# bldc_robot_main_adapter_board.net
KiCad netlist of a schematic drawn in Altium Designer
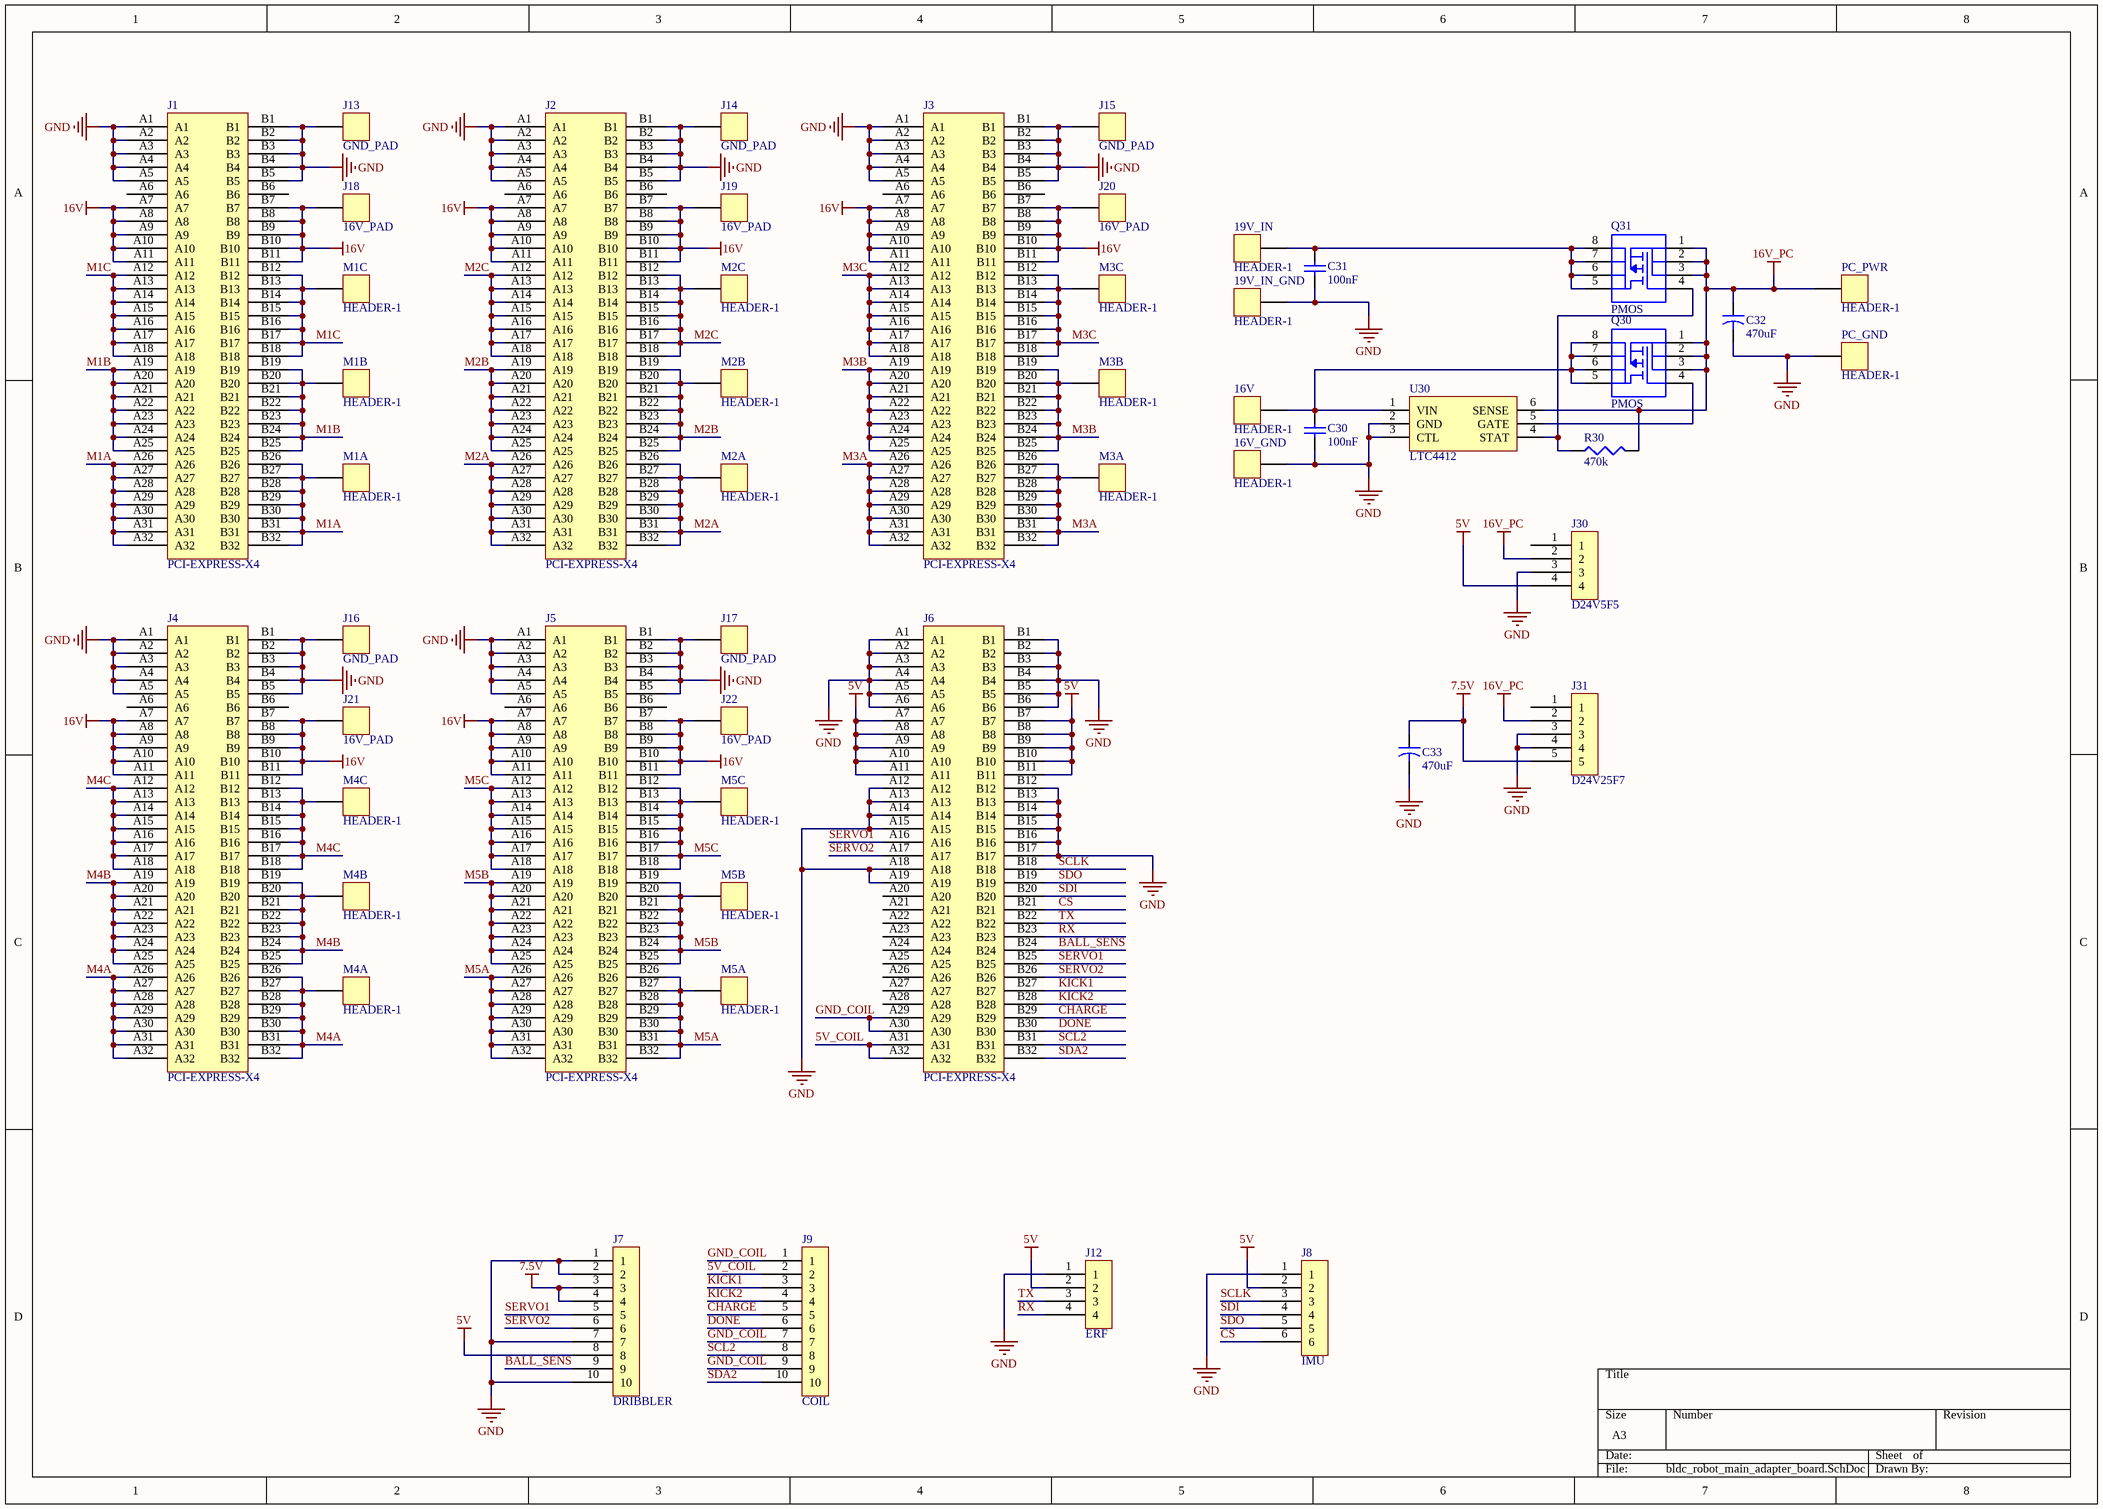
[diagram p0: bldc_robot_main_adapter_board.SchDoc]

(export (version "E")
  (design (tool "Eeschema 10.0.6"))
  (components
    (comp (ref "16V") (value "HEADER-1") (footprint "POWER-VIA") (libsource (lib "") (part "HEADER-1_1")))
    (comp (ref "16V_GND") (value "HEADER-1") (footprint "POWER-VIA") (libsource (lib "") (part "HEADER-1_1")))
    (comp (ref "19V_IN") (value "HEADER-1") (footprint "POWER-VIA") (libsource (lib "") (part "HEADER-1_1")))
    (comp (ref "19V_IN_GND")
      (value "HEADER-1")
      (footprint "POWER-VIA")
      (libsource (lib "") (part "HEADER-1_1"))
    )
    (comp (ref "C30")
      (value "100nF")
      (footprint "1608[0603]")
      (description "Capacitor (Semiconductor SIM Model)")
      (fields (field (name "PUBLISHER") "Altium Limited"))
      (libsource (lib "Miscellaneous Devices") (part "Cap Semi"))
    )
    (comp (ref "C31")
      (value "100nF")
      (footprint "1608[0603]")
      (description "Capacitor (Semiconductor SIM Model)")
      (fields (field (name "PUBLISHER") "Altium Limited"))
      (libsource (lib "Miscellaneous Devices") (part "Cap Semi"))
    )
    (comp (ref "C32")
      (value "470uF")
      (footprint "CAPR5-4X5")
      (description "Capacitor")
      (fields (field (name "PUBLISHER") "Altium Limited"))
      (libsource (lib "Miscellaneous Devices") (part "Cap2"))
    )
    (comp (ref "C33")
      (value "470uF")
      (footprint "CAPR5-4X5")
      (description "Capacitor")
      (fields (field (name "PUBLISHER") "Altium Limited"))
      (libsource (lib "Miscellaneous Devices") (part "Cap2"))
    )
    (comp (ref "J1")
      (value "PCI-EXPRESS-X4")
      (footprint "PCI-EXPRESS-X4-SOCKET")
      (libsource (lib "connectors") (part "PCI-EXPRESS-X4"))
    )
    (comp (ref "J2")
      (value "PCI-EXPRESS-X4")
      (footprint "PCI-EXPRESS-X4-SOCKET")
      (libsource (lib "connectors") (part "PCI-EXPRESS-X4"))
    )
    (comp (ref "J3")
      (value "PCI-EXPRESS-X4")
      (footprint "PCI-EXPRESS-X4-SOCKET")
      (libsource (lib "connectors") (part "PCI-EXPRESS-X4"))
    )
    (comp (ref "J4")
      (value "PCI-EXPRESS-X4")
      (footprint "PCI-EXPRESS-X4-SOCKET")
      (libsource (lib "connectors") (part "PCI-EXPRESS-X4"))
    )
    (comp (ref "J5")
      (value "PCI-EXPRESS-X4")
      (footprint "PCI-EXPRESS-X4-SOCKET")
      (libsource (lib "connectors") (part "PCI-EXPRESS-X4"))
    )
    (comp (ref "J6")
      (value "PCI-EXPRESS-X4")
      (footprint "PCI-EXPRESS-X4-SOCKET")
      (libsource (lib "connectors") (part "PCI-EXPRESS-X4"))
    )
    (comp (ref "J7")
      (value "DRIBBLER")
      (footprint "MICRO-MATCH-10")
      (libsource (lib "connectors") (part "HEADER-10"))
    )
    (comp (ref "J8")
      (value "IMU")
      (footprint "MICRO-MATCH-6")
      (libsource (lib "connectors") (part "HEADER-6"))
    )
    (comp (ref "J9")
      (value "COIL")
      (footprint "MICRO-MATCH-10")
      (libsource (lib "connectors") (part "HEADER-10"))
    )
    (comp (ref "J12")
      (value "ERF")
      (footprint "MICRO-MATCH-4")
      (libsource (lib "connectors") (part "HEADER-4"))
    )
    (comp (ref "J13")
      (value "GND_PAD")
      (footprint "POWER-PAD")
      (libsource (lib "connectors") (part "HEADER-1"))
    )
    (comp (ref "J14")
      (value "GND_PAD")
      (footprint "POWER-PAD")
      (libsource (lib "connectors") (part "HEADER-1"))
    )
    (comp (ref "J15")
      (value "GND_PAD")
      (footprint "POWER-PAD")
      (libsource (lib "connectors") (part "HEADER-1"))
    )
    (comp (ref "J16")
      (value "GND_PAD")
      (footprint "POWER-PAD")
      (libsource (lib "connectors") (part "HEADER-1"))
    )
    (comp (ref "J17")
      (value "GND_PAD")
      (footprint "POWER-PAD")
      (libsource (lib "connectors") (part "HEADER-1"))
    )
    (comp (ref "J18")
      (value "16V_PAD")
      (footprint "POWER-PAD")
      (libsource (lib "connectors") (part "HEADER-1"))
    )
    (comp (ref "J19")
      (value "16V_PAD")
      (footprint "POWER-PAD")
      (libsource (lib "connectors") (part "HEADER-1"))
    )
    (comp (ref "J20")
      (value "16V_PAD")
      (footprint "POWER-PAD")
      (libsource (lib "connectors") (part "HEADER-1"))
    )
    (comp (ref "J21")
      (value "16V_PAD")
      (footprint "POWER-PAD")
      (libsource (lib "connectors") (part "HEADER-1"))
    )
    (comp (ref "J22")
      (value "16V_PAD")
      (footprint "POWER-PAD")
      (libsource (lib "connectors") (part "HEADER-1"))
    )
    (comp (ref "J30")
      (value "D24V5F5")
      (footprint "PIN-HEADER-4")
      (libsource (lib "connectors") (part "HEADER-4"))
    )
    (comp (ref "J31")
      (value "D24V25F7")
      (footprint "PIN-HEADER-5")
      (libsource (lib "connectors") (part "HEADER-5"))
    )
    (comp (ref "M1A")
      (value "HEADER-1")
      (footprint "2MM-BULLET-VIA")
      (libsource (lib "connectors") (part "HEADER-1"))
    )
    (comp (ref "M1B")
      (value "HEADER-1")
      (footprint "2MM-BULLET-VIA")
      (libsource (lib "connectors") (part "HEADER-1"))
    )
    (comp (ref "M1C")
      (value "HEADER-1")
      (footprint "2MM-BULLET-VIA")
      (libsource (lib "connectors") (part "HEADER-1"))
    )
    (comp (ref "M2A")
      (value "HEADER-1")
      (footprint "2MM-BULLET-VIA")
      (libsource (lib "connectors") (part "HEADER-1"))
    )
    (comp (ref "M2B")
      (value "HEADER-1")
      (footprint "2MM-BULLET-VIA")
      (libsource (lib "connectors") (part "HEADER-1"))
    )
    (comp (ref "M2C")
      (value "HEADER-1")
      (footprint "2MM-BULLET-VIA")
      (libsource (lib "connectors") (part "HEADER-1"))
    )
    (comp (ref "M3A")
      (value "HEADER-1")
      (footprint "2MM-BULLET-VIA")
      (libsource (lib "connectors") (part "HEADER-1"))
    )
    (comp (ref "M3B")
      (value "HEADER-1")
      (footprint "2MM-BULLET-VIA")
      (libsource (lib "connectors") (part "HEADER-1"))
    )
    (comp (ref "M3C")
      (value "HEADER-1")
      (footprint "2MM-BULLET-VIA")
      (libsource (lib "connectors") (part "HEADER-1"))
    )
    (comp (ref "M4A")
      (value "HEADER-1")
      (footprint "2MM-BULLET-VIA")
      (libsource (lib "connectors") (part "HEADER-1"))
    )
    (comp (ref "M4B")
      (value "HEADER-1")
      (footprint "2MM-BULLET-VIA")
      (libsource (lib "connectors") (part "HEADER-1"))
    )
    (comp (ref "M4C")
      (value "HEADER-1")
      (footprint "2MM-BULLET-VIA")
      (libsource (lib "connectors") (part "HEADER-1"))
    )
    (comp (ref "M5A")
      (value "HEADER-1")
      (footprint "2MM-BULLET-VIA")
      (libsource (lib "connectors") (part "HEADER-1"))
    )
    (comp (ref "M5B")
      (value "HEADER-1")
      (footprint "2MM-BULLET-VIA")
      (libsource (lib "connectors") (part "HEADER-1"))
    )
    (comp (ref "M5C")
      (value "HEADER-1")
      (footprint "2MM-BULLET-VIA")
      (libsource (lib "connectors") (part "HEADER-1"))
    )
    (comp (ref "PC_GND")
      (value "HEADER-1")
      (footprint "POWER-VIA")
      (libsource (lib "connectors") (part "HEADER-1"))
    )
    (comp (ref "PC_PWR")
      (value "HEADER-1")
      (footprint "POWER-VIA")
      (libsource (lib "connectors") (part "HEADER-1"))
    )
    (comp (ref "Q30") (value "PMOS") (footprint "SO8") (libsource (lib "misc") (part "PMOS")))
    (comp (ref "Q31") (value "PMOS") (footprint "SO8") (libsource (lib "misc") (part "PMOS")))
    (comp (ref "R30")
      (value "470k")
      (footprint "J1-0603")
      (description "Resistor")
      (fields (field (name "PUBLISHER") "Altium Limited"))
      (libsource (lib "Miscellaneous Devices") (part "Res3"))
    )
    (comp (ref "U30") (value "LTC4412") (footprint "TSOT-23-6") (libsource (lib "digital") (part "LTC4412")))
  )
  (nets
    (net (code "1") (name "/5V_COIL") (class "Default")
      (node (ref "J6") (pin "A31") (pinfunction "A31_A31") (pintype "passive"))
      (node (ref "J6") (pin "A32") (pinfunction "A32_A32") (pintype "passive"))
      (node (ref "J9") (pin "2") (pinfunction "2_2") (pintype "passive"))
    )
    (net (code "2") (name "/BALL_SENS") (class "Default")
      (node (ref "J6") (pin "B24") (pinfunction "B24_B24") (pintype "passive"))
      (node (ref "J7") (pin "9") (pinfunction "9_9") (pintype "passive"))
    )
    (net (code "3") (name "/CHARGE") (class "Default")
      (node (ref "J6") (pin "B29") (pinfunction "B29_B29") (pintype "passive"))
      (node (ref "J9") (pin "5") (pinfunction "5_5") (pintype "passive"))
    )
    (net (code "4") (name "/CS") (class "Default")
      (node (ref "J6") (pin "B21") (pinfunction "B21_B21") (pintype "passive"))
      (node (ref "J8") (pin "6") (pinfunction "6_6") (pintype "passive"))
    )
    (net (code "5") (name "/DONE") (class "Default")
      (node (ref "J6") (pin "B30") (pinfunction "B30_B30") (pintype "passive"))
      (node (ref "J9") (pin "6") (pinfunction "6_6") (pintype "passive"))
    )
    (net (code "6") (name "/GND_COIL") (class "Default")
      (node (ref "J6") (pin "A29") (pinfunction "A29_A29") (pintype "passive"))
      (node (ref "J6") (pin "A30") (pinfunction "A30_A30") (pintype "passive"))
      (node (ref "J9") (pin "1") (pinfunction "1_1") (pintype "passive"))
      (node (ref "J9") (pin "7") (pinfunction "7_7") (pintype "passive"))
      (node (ref "J9") (pin "9") (pinfunction "9_9") (pintype "passive"))
    )
    (net (code "7") (name "/KICK1") (class "Default")
      (node (ref "J6") (pin "B27") (pinfunction "B27_B27") (pintype "passive"))
      (node (ref "J9") (pin "3") (pinfunction "3_3") (pintype "passive"))
    )
    (net (code "8") (name "/KICK2") (class "Default")
      (node (ref "J6") (pin "B28") (pinfunction "B28_B28") (pintype "passive"))
      (node (ref "J9") (pin "4") (pinfunction "4_4") (pintype "passive"))
    )
    (net (code "9") (name "/M1A") (class "Default")
      (node (ref "J1") (pin "A26") (pinfunction "A26_A26") (pintype "passive"))
      (node (ref "J1") (pin "A27") (pinfunction "A27_A27") (pintype "passive"))
      (node (ref "J1") (pin "A28") (pinfunction "A28_A28") (pintype "passive"))
      (node (ref "J1") (pin "A29") (pinfunction "A29_A29") (pintype "passive"))
      (node (ref "J1") (pin "A30") (pinfunction "A30_A30") (pintype "passive"))
      (node (ref "J1") (pin "A31") (pinfunction "A31_A31") (pintype "passive"))
      (node (ref "J1") (pin "A32") (pinfunction "A32_A32") (pintype "passive"))
      (node (ref "J1") (pin "B26") (pinfunction "B26_B26") (pintype "passive"))
      (node (ref "J1") (pin "B27") (pinfunction "B27_B27") (pintype "passive"))
      (node (ref "J1") (pin "B28") (pinfunction "B28_B28") (pintype "passive"))
      (node (ref "J1") (pin "B29") (pinfunction "B29_B29") (pintype "passive"))
      (node (ref "J1") (pin "B30") (pinfunction "B30_B30") (pintype "passive"))
      (node (ref "J1") (pin "B31") (pinfunction "B31_B31") (pintype "passive"))
      (node (ref "J1") (pin "B32") (pinfunction "B32_B32") (pintype "passive"))
      (node (ref "M1A") (pin "1") (pinfunction "1_1") (pintype "passive"))
    )
    (net (code "10") (name "/M1B") (class "Default")
      (node (ref "J1") (pin "A19") (pinfunction "A19_A19") (pintype "passive"))
      (node (ref "J1") (pin "A20") (pinfunction "A20_A20") (pintype "passive"))
      (node (ref "J1") (pin "A21") (pinfunction "A21_A21") (pintype "passive"))
      (node (ref "J1") (pin "A22") (pinfunction "A22_A22") (pintype "passive"))
      (node (ref "J1") (pin "A23") (pinfunction "A23_A23") (pintype "passive"))
      (node (ref "J1") (pin "A24") (pinfunction "A24_A24") (pintype "passive"))
      (node (ref "J1") (pin "A25") (pinfunction "A25_A25") (pintype "passive"))
      (node (ref "J1") (pin "B19") (pinfunction "B19_B19") (pintype "passive"))
      (node (ref "J1") (pin "B20") (pinfunction "B20_B20") (pintype "passive"))
      (node (ref "J1") (pin "B21") (pinfunction "B21_B21") (pintype "passive"))
      (node (ref "J1") (pin "B22") (pinfunction "B22_B22") (pintype "passive"))
      (node (ref "J1") (pin "B23") (pinfunction "B23_B23") (pintype "passive"))
      (node (ref "J1") (pin "B24") (pinfunction "B24_B24") (pintype "passive"))
      (node (ref "J1") (pin "B25") (pinfunction "B25_B25") (pintype "passive"))
      (node (ref "M1B") (pin "1") (pinfunction "1_1") (pintype "passive"))
    )
    (net (code "11") (name "/M1C") (class "Default")
      (node (ref "J1") (pin "A12") (pinfunction "A12_A12") (pintype "passive"))
      (node (ref "J1") (pin "A13") (pinfunction "A13_A13") (pintype "passive"))
      (node (ref "J1") (pin "A14") (pinfunction "A14_A14") (pintype "passive"))
      (node (ref "J1") (pin "A15") (pinfunction "A15_A15") (pintype "passive"))
      (node (ref "J1") (pin "A16") (pinfunction "A16_A16") (pintype "passive"))
      (node (ref "J1") (pin "A17") (pinfunction "A17_A17") (pintype "passive"))
      (node (ref "J1") (pin "A18") (pinfunction "A18_A18") (pintype "passive"))
      (node (ref "J1") (pin "B12") (pinfunction "B12_B12") (pintype "passive"))
      (node (ref "J1") (pin "B13") (pinfunction "B13_B13") (pintype "passive"))
      (node (ref "J1") (pin "B14") (pinfunction "B14_B14") (pintype "passive"))
      (node (ref "J1") (pin "B15") (pinfunction "B15_B15") (pintype "passive"))
      (node (ref "J1") (pin "B16") (pinfunction "B16_B16") (pintype "passive"))
      (node (ref "J1") (pin "B17") (pinfunction "B17_B17") (pintype "passive"))
      (node (ref "J1") (pin "B18") (pinfunction "B18_B18") (pintype "passive"))
      (node (ref "M1C") (pin "1") (pinfunction "1_1") (pintype "passive"))
    )
    (net (code "12") (name "/M2A") (class "Default")
      (node (ref "J2") (pin "A26") (pinfunction "A26_A26") (pintype "passive"))
      (node (ref "J2") (pin "A27") (pinfunction "A27_A27") (pintype "passive"))
      (node (ref "J2") (pin "A28") (pinfunction "A28_A28") (pintype "passive"))
      (node (ref "J2") (pin "A29") (pinfunction "A29_A29") (pintype "passive"))
      (node (ref "J2") (pin "A30") (pinfunction "A30_A30") (pintype "passive"))
      (node (ref "J2") (pin "A31") (pinfunction "A31_A31") (pintype "passive"))
      (node (ref "J2") (pin "A32") (pinfunction "A32_A32") (pintype "passive"))
      (node (ref "J2") (pin "B26") (pinfunction "B26_B26") (pintype "passive"))
      (node (ref "J2") (pin "B27") (pinfunction "B27_B27") (pintype "passive"))
      (node (ref "J2") (pin "B28") (pinfunction "B28_B28") (pintype "passive"))
      (node (ref "J2") (pin "B29") (pinfunction "B29_B29") (pintype "passive"))
      (node (ref "J2") (pin "B30") (pinfunction "B30_B30") (pintype "passive"))
      (node (ref "J2") (pin "B31") (pinfunction "B31_B31") (pintype "passive"))
      (node (ref "J2") (pin "B32") (pinfunction "B32_B32") (pintype "passive"))
      (node (ref "M2A") (pin "1") (pinfunction "1_1") (pintype "passive"))
    )
    (net (code "13") (name "/M2B") (class "Default")
      (node (ref "J2") (pin "A19") (pinfunction "A19_A19") (pintype "passive"))
      (node (ref "J2") (pin "A20") (pinfunction "A20_A20") (pintype "passive"))
      (node (ref "J2") (pin "A21") (pinfunction "A21_A21") (pintype "passive"))
      (node (ref "J2") (pin "A22") (pinfunction "A22_A22") (pintype "passive"))
      (node (ref "J2") (pin "A23") (pinfunction "A23_A23") (pintype "passive"))
      (node (ref "J2") (pin "A24") (pinfunction "A24_A24") (pintype "passive"))
      (node (ref "J2") (pin "A25") (pinfunction "A25_A25") (pintype "passive"))
      (node (ref "J2") (pin "B19") (pinfunction "B19_B19") (pintype "passive"))
      (node (ref "J2") (pin "B20") (pinfunction "B20_B20") (pintype "passive"))
      (node (ref "J2") (pin "B21") (pinfunction "B21_B21") (pintype "passive"))
      (node (ref "J2") (pin "B22") (pinfunction "B22_B22") (pintype "passive"))
      (node (ref "J2") (pin "B23") (pinfunction "B23_B23") (pintype "passive"))
      (node (ref "J2") (pin "B24") (pinfunction "B24_B24") (pintype "passive"))
      (node (ref "J2") (pin "B25") (pinfunction "B25_B25") (pintype "passive"))
      (node (ref "M2B") (pin "1") (pinfunction "1_1") (pintype "passive"))
    )
    (net (code "14") (name "/M2C") (class "Default")
      (node (ref "J2") (pin "A12") (pinfunction "A12_A12") (pintype "passive"))
      (node (ref "J2") (pin "A13") (pinfunction "A13_A13") (pintype "passive"))
      (node (ref "J2") (pin "A14") (pinfunction "A14_A14") (pintype "passive"))
      (node (ref "J2") (pin "A15") (pinfunction "A15_A15") (pintype "passive"))
      (node (ref "J2") (pin "A16") (pinfunction "A16_A16") (pintype "passive"))
      (node (ref "J2") (pin "A17") (pinfunction "A17_A17") (pintype "passive"))
      (node (ref "J2") (pin "A18") (pinfunction "A18_A18") (pintype "passive"))
      (node (ref "J2") (pin "B12") (pinfunction "B12_B12") (pintype "passive"))
      (node (ref "J2") (pin "B13") (pinfunction "B13_B13") (pintype "passive"))
      (node (ref "J2") (pin "B14") (pinfunction "B14_B14") (pintype "passive"))
      (node (ref "J2") (pin "B15") (pinfunction "B15_B15") (pintype "passive"))
      (node (ref "J2") (pin "B16") (pinfunction "B16_B16") (pintype "passive"))
      (node (ref "J2") (pin "B17") (pinfunction "B17_B17") (pintype "passive"))
      (node (ref "J2") (pin "B18") (pinfunction "B18_B18") (pintype "passive"))
      (node (ref "M2C") (pin "1") (pinfunction "1_1") (pintype "passive"))
    )
    (net (code "15") (name "/M3A") (class "Default")
      (node (ref "J3") (pin "A26") (pinfunction "A26_A26") (pintype "passive"))
      (node (ref "J3") (pin "A27") (pinfunction "A27_A27") (pintype "passive"))
      (node (ref "J3") (pin "A28") (pinfunction "A28_A28") (pintype "passive"))
      (node (ref "J3") (pin "A29") (pinfunction "A29_A29") (pintype "passive"))
      (node (ref "J3") (pin "A30") (pinfunction "A30_A30") (pintype "passive"))
      (node (ref "J3") (pin "A31") (pinfunction "A31_A31") (pintype "passive"))
      (node (ref "J3") (pin "A32") (pinfunction "A32_A32") (pintype "passive"))
      (node (ref "J3") (pin "B26") (pinfunction "B26_B26") (pintype "passive"))
      (node (ref "J3") (pin "B27") (pinfunction "B27_B27") (pintype "passive"))
      (node (ref "J3") (pin "B28") (pinfunction "B28_B28") (pintype "passive"))
      (node (ref "J3") (pin "B29") (pinfunction "B29_B29") (pintype "passive"))
      (node (ref "J3") (pin "B30") (pinfunction "B30_B30") (pintype "passive"))
      (node (ref "J3") (pin "B31") (pinfunction "B31_B31") (pintype "passive"))
      (node (ref "J3") (pin "B32") (pinfunction "B32_B32") (pintype "passive"))
      (node (ref "M3A") (pin "1") (pinfunction "1_1") (pintype "passive"))
    )
    (net (code "16") (name "/M3B") (class "Default")
      (node (ref "J3") (pin "A19") (pinfunction "A19_A19") (pintype "passive"))
      (node (ref "J3") (pin "A20") (pinfunction "A20_A20") (pintype "passive"))
      (node (ref "J3") (pin "A21") (pinfunction "A21_A21") (pintype "passive"))
      (node (ref "J3") (pin "A22") (pinfunction "A22_A22") (pintype "passive"))
      (node (ref "J3") (pin "A23") (pinfunction "A23_A23") (pintype "passive"))
      (node (ref "J3") (pin "A24") (pinfunction "A24_A24") (pintype "passive"))
      (node (ref "J3") (pin "A25") (pinfunction "A25_A25") (pintype "passive"))
      (node (ref "J3") (pin "B19") (pinfunction "B19_B19") (pintype "passive"))
      (node (ref "J3") (pin "B20") (pinfunction "B20_B20") (pintype "passive"))
      (node (ref "J3") (pin "B21") (pinfunction "B21_B21") (pintype "passive"))
      (node (ref "J3") (pin "B22") (pinfunction "B22_B22") (pintype "passive"))
      (node (ref "J3") (pin "B23") (pinfunction "B23_B23") (pintype "passive"))
      (node (ref "J3") (pin "B24") (pinfunction "B24_B24") (pintype "passive"))
      (node (ref "J3") (pin "B25") (pinfunction "B25_B25") (pintype "passive"))
      (node (ref "M3B") (pin "1") (pinfunction "1_1") (pintype "passive"))
    )
    (net (code "17") (name "/M3C") (class "Default")
      (node (ref "J3") (pin "A12") (pinfunction "A12_A12") (pintype "passive"))
      (node (ref "J3") (pin "A13") (pinfunction "A13_A13") (pintype "passive"))
      (node (ref "J3") (pin "A14") (pinfunction "A14_A14") (pintype "passive"))
      (node (ref "J3") (pin "A15") (pinfunction "A15_A15") (pintype "passive"))
      (node (ref "J3") (pin "A16") (pinfunction "A16_A16") (pintype "passive"))
      (node (ref "J3") (pin "A17") (pinfunction "A17_A17") (pintype "passive"))
      (node (ref "J3") (pin "A18") (pinfunction "A18_A18") (pintype "passive"))
      (node (ref "J3") (pin "B12") (pinfunction "B12_B12") (pintype "passive"))
      (node (ref "J3") (pin "B13") (pinfunction "B13_B13") (pintype "passive"))
      (node (ref "J3") (pin "B14") (pinfunction "B14_B14") (pintype "passive"))
      (node (ref "J3") (pin "B15") (pinfunction "B15_B15") (pintype "passive"))
      (node (ref "J3") (pin "B16") (pinfunction "B16_B16") (pintype "passive"))
      (node (ref "J3") (pin "B17") (pinfunction "B17_B17") (pintype "passive"))
      (node (ref "J3") (pin "B18") (pinfunction "B18_B18") (pintype "passive"))
      (node (ref "M3C") (pin "1") (pinfunction "1_1") (pintype "passive"))
    )
    (net (code "18") (name "/M4A") (class "Default")
      (node (ref "J4") (pin "A26") (pinfunction "A26_A26") (pintype "passive"))
      (node (ref "J4") (pin "A27") (pinfunction "A27_A27") (pintype "passive"))
      (node (ref "J4") (pin "A28") (pinfunction "A28_A28") (pintype "passive"))
      (node (ref "J4") (pin "A29") (pinfunction "A29_A29") (pintype "passive"))
      (node (ref "J4") (pin "A30") (pinfunction "A30_A30") (pintype "passive"))
      (node (ref "J4") (pin "A31") (pinfunction "A31_A31") (pintype "passive"))
      (node (ref "J4") (pin "A32") (pinfunction "A32_A32") (pintype "passive"))
      (node (ref "J4") (pin "B26") (pinfunction "B26_B26") (pintype "passive"))
      (node (ref "J4") (pin "B27") (pinfunction "B27_B27") (pintype "passive"))
      (node (ref "J4") (pin "B28") (pinfunction "B28_B28") (pintype "passive"))
      (node (ref "J4") (pin "B29") (pinfunction "B29_B29") (pintype "passive"))
      (node (ref "J4") (pin "B30") (pinfunction "B30_B30") (pintype "passive"))
      (node (ref "J4") (pin "B31") (pinfunction "B31_B31") (pintype "passive"))
      (node (ref "J4") (pin "B32") (pinfunction "B32_B32") (pintype "passive"))
      (node (ref "M4A") (pin "1") (pinfunction "1_1") (pintype "passive"))
    )
    (net (code "19") (name "/M4B") (class "Default")
      (node (ref "J4") (pin "A19") (pinfunction "A19_A19") (pintype "passive"))
      (node (ref "J4") (pin "A20") (pinfunction "A20_A20") (pintype "passive"))
      (node (ref "J4") (pin "A21") (pinfunction "A21_A21") (pintype "passive"))
      (node (ref "J4") (pin "A22") (pinfunction "A22_A22") (pintype "passive"))
      (node (ref "J4") (pin "A23") (pinfunction "A23_A23") (pintype "passive"))
      (node (ref "J4") (pin "A24") (pinfunction "A24_A24") (pintype "passive"))
      (node (ref "J4") (pin "A25") (pinfunction "A25_A25") (pintype "passive"))
      (node (ref "J4") (pin "B19") (pinfunction "B19_B19") (pintype "passive"))
      (node (ref "J4") (pin "B20") (pinfunction "B20_B20") (pintype "passive"))
      (node (ref "J4") (pin "B21") (pinfunction "B21_B21") (pintype "passive"))
      (node (ref "J4") (pin "B22") (pinfunction "B22_B22") (pintype "passive"))
      (node (ref "J4") (pin "B23") (pinfunction "B23_B23") (pintype "passive"))
      (node (ref "J4") (pin "B24") (pinfunction "B24_B24") (pintype "passive"))
      (node (ref "J4") (pin "B25") (pinfunction "B25_B25") (pintype "passive"))
      (node (ref "M4B") (pin "1") (pinfunction "1_1") (pintype "passive"))
    )
    (net (code "20") (name "/M4C") (class "Default")
      (node (ref "J4") (pin "A12") (pinfunction "A12_A12") (pintype "passive"))
      (node (ref "J4") (pin "A13") (pinfunction "A13_A13") (pintype "passive"))
      (node (ref "J4") (pin "A14") (pinfunction "A14_A14") (pintype "passive"))
      (node (ref "J4") (pin "A15") (pinfunction "A15_A15") (pintype "passive"))
      (node (ref "J4") (pin "A16") (pinfunction "A16_A16") (pintype "passive"))
      (node (ref "J4") (pin "A17") (pinfunction "A17_A17") (pintype "passive"))
      (node (ref "J4") (pin "A18") (pinfunction "A18_A18") (pintype "passive"))
      (node (ref "J4") (pin "B12") (pinfunction "B12_B12") (pintype "passive"))
      (node (ref "J4") (pin "B13") (pinfunction "B13_B13") (pintype "passive"))
      (node (ref "J4") (pin "B14") (pinfunction "B14_B14") (pintype "passive"))
      (node (ref "J4") (pin "B15") (pinfunction "B15_B15") (pintype "passive"))
      (node (ref "J4") (pin "B16") (pinfunction "B16_B16") (pintype "passive"))
      (node (ref "J4") (pin "B17") (pinfunction "B17_B17") (pintype "passive"))
      (node (ref "J4") (pin "B18") (pinfunction "B18_B18") (pintype "passive"))
      (node (ref "M4C") (pin "1") (pinfunction "1_1") (pintype "passive"))
    )
    (net (code "21") (name "/M5A") (class "Default")
      (node (ref "J5") (pin "A26") (pinfunction "A26_A26") (pintype "passive"))
      (node (ref "J5") (pin "A27") (pinfunction "A27_A27") (pintype "passive"))
      (node (ref "J5") (pin "A28") (pinfunction "A28_A28") (pintype "passive"))
      (node (ref "J5") (pin "A29") (pinfunction "A29_A29") (pintype "passive"))
      (node (ref "J5") (pin "A30") (pinfunction "A30_A30") (pintype "passive"))
      (node (ref "J5") (pin "A31") (pinfunction "A31_A31") (pintype "passive"))
      (node (ref "J5") (pin "A32") (pinfunction "A32_A32") (pintype "passive"))
      (node (ref "J5") (pin "B26") (pinfunction "B26_B26") (pintype "passive"))
      (node (ref "J5") (pin "B27") (pinfunction "B27_B27") (pintype "passive"))
      (node (ref "J5") (pin "B28") (pinfunction "B28_B28") (pintype "passive"))
      (node (ref "J5") (pin "B29") (pinfunction "B29_B29") (pintype "passive"))
      (node (ref "J5") (pin "B30") (pinfunction "B30_B30") (pintype "passive"))
      (node (ref "J5") (pin "B31") (pinfunction "B31_B31") (pintype "passive"))
      (node (ref "J5") (pin "B32") (pinfunction "B32_B32") (pintype "passive"))
      (node (ref "M5A") (pin "1") (pinfunction "1_1") (pintype "passive"))
    )
    (net (code "22") (name "/M5B") (class "Default")
      (node (ref "J5") (pin "A19") (pinfunction "A19_A19") (pintype "passive"))
      (node (ref "J5") (pin "A20") (pinfunction "A20_A20") (pintype "passive"))
      (node (ref "J5") (pin "A21") (pinfunction "A21_A21") (pintype "passive"))
      (node (ref "J5") (pin "A22") (pinfunction "A22_A22") (pintype "passive"))
      (node (ref "J5") (pin "A23") (pinfunction "A23_A23") (pintype "passive"))
      (node (ref "J5") (pin "A24") (pinfunction "A24_A24") (pintype "passive"))
      (node (ref "J5") (pin "A25") (pinfunction "A25_A25") (pintype "passive"))
      (node (ref "J5") (pin "B19") (pinfunction "B19_B19") (pintype "passive"))
      (node (ref "J5") (pin "B20") (pinfunction "B20_B20") (pintype "passive"))
      (node (ref "J5") (pin "B21") (pinfunction "B21_B21") (pintype "passive"))
      (node (ref "J5") (pin "B22") (pinfunction "B22_B22") (pintype "passive"))
      (node (ref "J5") (pin "B23") (pinfunction "B23_B23") (pintype "passive"))
      (node (ref "J5") (pin "B24") (pinfunction "B24_B24") (pintype "passive"))
      (node (ref "J5") (pin "B25") (pinfunction "B25_B25") (pintype "passive"))
      (node (ref "M5B") (pin "1") (pinfunction "1_1") (pintype "passive"))
    )
    (net (code "23") (name "/M5C") (class "Default")
      (node (ref "J5") (pin "A12") (pinfunction "A12_A12") (pintype "passive"))
      (node (ref "J5") (pin "A13") (pinfunction "A13_A13") (pintype "passive"))
      (node (ref "J5") (pin "A14") (pinfunction "A14_A14") (pintype "passive"))
      (node (ref "J5") (pin "A15") (pinfunction "A15_A15") (pintype "passive"))
      (node (ref "J5") (pin "A16") (pinfunction "A16_A16") (pintype "passive"))
      (node (ref "J5") (pin "A17") (pinfunction "A17_A17") (pintype "passive"))
      (node (ref "J5") (pin "A18") (pinfunction "A18_A18") (pintype "passive"))
      (node (ref "J5") (pin "B12") (pinfunction "B12_B12") (pintype "passive"))
      (node (ref "J5") (pin "B13") (pinfunction "B13_B13") (pintype "passive"))
      (node (ref "J5") (pin "B14") (pinfunction "B14_B14") (pintype "passive"))
      (node (ref "J5") (pin "B15") (pinfunction "B15_B15") (pintype "passive"))
      (node (ref "J5") (pin "B16") (pinfunction "B16_B16") (pintype "passive"))
      (node (ref "J5") (pin "B17") (pinfunction "B17_B17") (pintype "passive"))
      (node (ref "J5") (pin "B18") (pinfunction "B18_B18") (pintype "passive"))
      (node (ref "M5C") (pin "1") (pinfunction "1_1") (pintype "passive"))
    )
    (net (code "24") (name "/RX") (class "Default")
      (node (ref "J12") (pin "4") (pinfunction "4_4") (pintype "passive"))
      (node (ref "J6") (pin "B23") (pinfunction "B23_B23") (pintype "passive"))
    )
    (net (code "25") (name "/SCL2") (class "Default")
      (node (ref "J6") (pin "B31") (pinfunction "B31_B31") (pintype "passive"))
      (node (ref "J9") (pin "8") (pinfunction "8_8") (pintype "passive"))
    )
    (net (code "26") (name "/SCLK") (class "Default")
      (node (ref "J6") (pin "B18") (pinfunction "B18_B18") (pintype "passive"))
      (node (ref "J8") (pin "3") (pinfunction "3_3") (pintype "passive"))
    )
    (net (code "27") (name "/SDA2") (class "Default")
      (node (ref "J6") (pin "B32") (pinfunction "B32_B32") (pintype "passive"))
      (node (ref "J9") (pin "10") (pinfunction "10_10") (pintype "passive"))
    )
    (net (code "28") (name "/SDI") (class "Default")
      (node (ref "J6") (pin "B20") (pinfunction "B20_B20") (pintype "passive"))
      (node (ref "J8") (pin "4") (pinfunction "4_4") (pintype "passive"))
    )
    (net (code "29") (name "/SDO") (class "Default")
      (node (ref "J6") (pin "B19") (pinfunction "B19_B19") (pintype "passive"))
      (node (ref "J8") (pin "5") (pinfunction "5_5") (pintype "passive"))
    )
    (net (code "30") (name "/SERVO1") (class "Default")
      (node (ref "J6") (pin "A16") (pinfunction "A16_A16") (pintype "passive"))
      (node (ref "J6") (pin "B25") (pinfunction "B25_B25") (pintype "passive"))
      (node (ref "J7") (pin "5") (pinfunction "5_5") (pintype "passive"))
    )
    (net (code "31") (name "/SERVO2") (class "Default")
      (node (ref "J6") (pin "A17") (pinfunction "A17_A17") (pintype "passive"))
      (node (ref "J6") (pin "B26") (pinfunction "B26_B26") (pintype "passive"))
      (node (ref "J7") (pin "6") (pinfunction "6_6") (pintype "passive"))
    )
    (net (code "32") (name "/TX") (class "Default")
      (node (ref "J12") (pin "3") (pinfunction "3_3") (pintype "passive"))
      (node (ref "J6") (pin "B22") (pinfunction "B22_B22") (pintype "passive"))
    )
    (net (code "33") (name "5V") (class "Default")
      (node (ref "J12") (pin "2") (pinfunction "2_2") (pintype "passive"))
      (node (ref "J30") (pin "4") (pinfunction "4_4") (pintype "passive"))
      (node (ref "J6") (pin "A10") (pinfunction "A10_A10") (pintype "passive"))
      (node (ref "J6") (pin "A11") (pinfunction "A11_A11") (pintype "passive"))
      (node (ref "J6") (pin "A7") (pinfunction "A7_A7") (pintype "passive"))
      (node (ref "J6") (pin "A8") (pinfunction "A8_A8") (pintype "passive"))
      (node (ref "J6") (pin "A9") (pinfunction "A9_A9") (pintype "passive"))
      (node (ref "J6") (pin "B10") (pinfunction "B10_B10") (pintype "passive"))
      (node (ref "J6") (pin "B11") (pinfunction "B11_B11") (pintype "passive"))
      (node (ref "J6") (pin "B7") (pinfunction "B7_B7") (pintype "passive"))
      (node (ref "J6") (pin "B8") (pinfunction "B8_B8") (pintype "passive"))
      (node (ref "J6") (pin "B9") (pinfunction "B9_B9") (pintype "passive"))
      (node (ref "J7") (pin "8") (pinfunction "8_8") (pintype "passive"))
      (node (ref "J8") (pin "2") (pinfunction "2_2") (pintype "passive"))
    )
    (net (code "34") (name "7.5V") (class "Default")
      (node (ref "C33") (pin "1") (pinfunction "1_1") (pintype "passive"))
      (node (ref "J31") (pin "5") (pinfunction "5_5") (pintype "passive"))
      (node (ref "J7") (pin "3") (pinfunction "3_3") (pintype "passive"))
      (node (ref "J7") (pin "4") (pinfunction "4_4") (pintype "passive"))
    )
    (net (code "35") (name "16V") (class "Default")
      (node (ref "J1") (pin "A10") (pinfunction "A10_A10") (pintype "passive"))
      (node (ref "J1") (pin "A11") (pinfunction "A11_A11") (pintype "passive"))
      (node (ref "J1") (pin "A7") (pinfunction "A7_A7") (pintype "passive"))
      (node (ref "J1") (pin "A8") (pinfunction "A8_A8") (pintype "passive"))
      (node (ref "J1") (pin "A9") (pinfunction "A9_A9") (pintype "passive"))
      (node (ref "J1") (pin "B10") (pinfunction "B10_B10") (pintype "passive"))
      (node (ref "J1") (pin "B11") (pinfunction "B11_B11") (pintype "passive"))
      (node (ref "J1") (pin "B7") (pinfunction "B7_B7") (pintype "passive"))
      (node (ref "J1") (pin "B8") (pinfunction "B8_B8") (pintype "passive"))
      (node (ref "J1") (pin "B9") (pinfunction "B9_B9") (pintype "passive"))
      (node (ref "J18") (pin "1") (pinfunction "1_1") (pintype "passive"))
      (node (ref "J19") (pin "1") (pinfunction "1_1") (pintype "passive"))
      (node (ref "J2") (pin "A10") (pinfunction "A10_A10") (pintype "passive"))
      (node (ref "J2") (pin "A11") (pinfunction "A11_A11") (pintype "passive"))
      (node (ref "J2") (pin "A7") (pinfunction "A7_A7") (pintype "passive"))
      (node (ref "J2") (pin "A8") (pinfunction "A8_A8") (pintype "passive"))
      (node (ref "J2") (pin "A9") (pinfunction "A9_A9") (pintype "passive"))
      (node (ref "J2") (pin "B10") (pinfunction "B10_B10") (pintype "passive"))
      (node (ref "J2") (pin "B11") (pinfunction "B11_B11") (pintype "passive"))
      (node (ref "J2") (pin "B7") (pinfunction "B7_B7") (pintype "passive"))
      (node (ref "J2") (pin "B8") (pinfunction "B8_B8") (pintype "passive"))
      (node (ref "J2") (pin "B9") (pinfunction "B9_B9") (pintype "passive"))
      (node (ref "J20") (pin "1") (pinfunction "1_1") (pintype "passive"))
      (node (ref "J21") (pin "1") (pinfunction "1_1") (pintype "passive"))
      (node (ref "J22") (pin "1") (pinfunction "1_1") (pintype "passive"))
      (node (ref "J3") (pin "A10") (pinfunction "A10_A10") (pintype "passive"))
      (node (ref "J3") (pin "A11") (pinfunction "A11_A11") (pintype "passive"))
      (node (ref "J3") (pin "A7") (pinfunction "A7_A7") (pintype "passive"))
      (node (ref "J3") (pin "A8") (pinfunction "A8_A8") (pintype "passive"))
      (node (ref "J3") (pin "A9") (pinfunction "A9_A9") (pintype "passive"))
      (node (ref "J3") (pin "B10") (pinfunction "B10_B10") (pintype "passive"))
      (node (ref "J3") (pin "B11") (pinfunction "B11_B11") (pintype "passive"))
      (node (ref "J3") (pin "B7") (pinfunction "B7_B7") (pintype "passive"))
      (node (ref "J3") (pin "B8") (pinfunction "B8_B8") (pintype "passive"))
      (node (ref "J3") (pin "B9") (pinfunction "B9_B9") (pintype "passive"))
      (node (ref "J4") (pin "A10") (pinfunction "A10_A10") (pintype "passive"))
      (node (ref "J4") (pin "A11") (pinfunction "A11_A11") (pintype "passive"))
      (node (ref "J4") (pin "A7") (pinfunction "A7_A7") (pintype "passive"))
      (node (ref "J4") (pin "A8") (pinfunction "A8_A8") (pintype "passive"))
      (node (ref "J4") (pin "A9") (pinfunction "A9_A9") (pintype "passive"))
      (node (ref "J4") (pin "B10") (pinfunction "B10_B10") (pintype "passive"))
      (node (ref "J4") (pin "B11") (pinfunction "B11_B11") (pintype "passive"))
      (node (ref "J4") (pin "B7") (pinfunction "B7_B7") (pintype "passive"))
      (node (ref "J4") (pin "B8") (pinfunction "B8_B8") (pintype "passive"))
      (node (ref "J4") (pin "B9") (pinfunction "B9_B9") (pintype "passive"))
      (node (ref "J5") (pin "A10") (pinfunction "A10_A10") (pintype "passive"))
      (node (ref "J5") (pin "A11") (pinfunction "A11_A11") (pintype "passive"))
      (node (ref "J5") (pin "A7") (pinfunction "A7_A7") (pintype "passive"))
      (node (ref "J5") (pin "A8") (pinfunction "A8_A8") (pintype "passive"))
      (node (ref "J5") (pin "A9") (pinfunction "A9_A9") (pintype "passive"))
      (node (ref "J5") (pin "B10") (pinfunction "B10_B10") (pintype "passive"))
      (node (ref "J5") (pin "B11") (pinfunction "B11_B11") (pintype "passive"))
      (node (ref "J5") (pin "B7") (pinfunction "B7_B7") (pintype "passive"))
      (node (ref "J5") (pin "B8") (pinfunction "B8_B8") (pintype "passive"))
      (node (ref "J5") (pin "B9") (pinfunction "B9_B9") (pintype "passive"))
    )
    (net (code "36") (name "16V_PC") (class "Default")
      (node (ref "C32") (pin "1") (pinfunction "1_1") (pintype "passive"))
      (node (ref "J30") (pin "2") (pinfunction "2_2") (pintype "passive"))
      (node (ref "J31") (pin "2") (pinfunction "2_2") (pintype "passive"))
      (node (ref "PC_PWR") (pin "1") (pinfunction "1_1") (pintype "passive"))
      (node (ref "Q30") (pin "1") (pinfunction "1_1") (pintype "passive"))
      (node (ref "Q30") (pin "2") (pinfunction "2_2") (pintype "passive"))
      (node (ref "Q30") (pin "3") (pinfunction "3_3") (pintype "passive"))
      (node (ref "Q31") (pin "1") (pinfunction "1_1") (pintype "passive"))
      (node (ref "Q31") (pin "2") (pinfunction "2_2") (pintype "passive"))
      (node (ref "Q31") (pin "3") (pinfunction "3_3") (pintype "passive"))
      (node (ref "R30") (pin "2") (pinfunction "2_2") (pintype "passive"))
      (node (ref "U30") (pin "6") (pinfunction "SENSE_6") (pintype "passive"))
    )
    (net (code "37") (name "GND") (class "Default")
      (node (ref "16V_GND") (pin "1") (pinfunction "1_1") (pintype "passive"))
      (node (ref "19V_IN_GND") (pin "1") (pinfunction "1_1") (pintype "passive"))
      (node (ref "C30") (pin "2") (pinfunction "2_2") (pintype "passive"))
      (node (ref "C31") (pin "2") (pinfunction "2_2") (pintype "passive"))
      (node (ref "C32") (pin "2") (pinfunction "2_2") (pintype "passive"))
      (node (ref "C33") (pin "2") (pinfunction "2_2") (pintype "passive"))
      (node (ref "J1") (pin "A1") (pinfunction "A1_A1") (pintype "passive"))
      (node (ref "J1") (pin "A2") (pinfunction "A2_A2") (pintype "passive"))
      (node (ref "J1") (pin "A3") (pinfunction "A3_A3") (pintype "passive"))
      (node (ref "J1") (pin "A4") (pinfunction "A4_A4") (pintype "passive"))
      (node (ref "J1") (pin "A5") (pinfunction "A5_A5") (pintype "passive"))
      (node (ref "J1") (pin "B1") (pinfunction "B1_B1") (pintype "passive"))
      (node (ref "J1") (pin "B2") (pinfunction "B2_B2") (pintype "passive"))
      (node (ref "J1") (pin "B3") (pinfunction "B3_B3") (pintype "passive"))
      (node (ref "J1") (pin "B4") (pinfunction "B4_B4") (pintype "passive"))
      (node (ref "J1") (pin "B5") (pinfunction "B5_B5") (pintype "passive"))
      (node (ref "J12") (pin "1") (pinfunction "1_1") (pintype "passive"))
      (node (ref "J13") (pin "1") (pinfunction "1_1") (pintype "passive"))
      (node (ref "J14") (pin "1") (pinfunction "1_1") (pintype "passive"))
      (node (ref "J15") (pin "1") (pinfunction "1_1") (pintype "passive"))
      (node (ref "J16") (pin "1") (pinfunction "1_1") (pintype "passive"))
      (node (ref "J17") (pin "1") (pinfunction "1_1") (pintype "passive"))
      (node (ref "J2") (pin "A1") (pinfunction "A1_A1") (pintype "passive"))
      (node (ref "J2") (pin "A2") (pinfunction "A2_A2") (pintype "passive"))
      (node (ref "J2") (pin "A3") (pinfunction "A3_A3") (pintype "passive"))
      (node (ref "J2") (pin "A4") (pinfunction "A4_A4") (pintype "passive"))
      (node (ref "J2") (pin "A5") (pinfunction "A5_A5") (pintype "passive"))
      (node (ref "J2") (pin "B1") (pinfunction "B1_B1") (pintype "passive"))
      (node (ref "J2") (pin "B2") (pinfunction "B2_B2") (pintype "passive"))
      (node (ref "J2") (pin "B3") (pinfunction "B3_B3") (pintype "passive"))
      (node (ref "J2") (pin "B4") (pinfunction "B4_B4") (pintype "passive"))
      (node (ref "J2") (pin "B5") (pinfunction "B5_B5") (pintype "passive"))
      (node (ref "J3") (pin "A1") (pinfunction "A1_A1") (pintype "passive"))
      (node (ref "J3") (pin "A2") (pinfunction "A2_A2") (pintype "passive"))
      (node (ref "J3") (pin "A3") (pinfunction "A3_A3") (pintype "passive"))
      (node (ref "J3") (pin "A4") (pinfunction "A4_A4") (pintype "passive"))
      (node (ref "J3") (pin "A5") (pinfunction "A5_A5") (pintype "passive"))
      (node (ref "J3") (pin "B1") (pinfunction "B1_B1") (pintype "passive"))
      (node (ref "J3") (pin "B2") (pinfunction "B2_B2") (pintype "passive"))
      (node (ref "J3") (pin "B3") (pinfunction "B3_B3") (pintype "passive"))
      (node (ref "J3") (pin "B4") (pinfunction "B4_B4") (pintype "passive"))
      (node (ref "J3") (pin "B5") (pinfunction "B5_B5") (pintype "passive"))
      (node (ref "J30") (pin "3") (pinfunction "3_3") (pintype "passive"))
      (node (ref "J31") (pin "3") (pinfunction "3_3") (pintype "passive"))
      (node (ref "J31") (pin "4") (pinfunction "4_4") (pintype "passive"))
      (node (ref "J4") (pin "A1") (pinfunction "A1_A1") (pintype "passive"))
      (node (ref "J4") (pin "A2") (pinfunction "A2_A2") (pintype "passive"))
      (node (ref "J4") (pin "A3") (pinfunction "A3_A3") (pintype "passive"))
      (node (ref "J4") (pin "A4") (pinfunction "A4_A4") (pintype "passive"))
      (node (ref "J4") (pin "A5") (pinfunction "A5_A5") (pintype "passive"))
      (node (ref "J4") (pin "B1") (pinfunction "B1_B1") (pintype "passive"))
      (node (ref "J4") (pin "B2") (pinfunction "B2_B2") (pintype "passive"))
      (node (ref "J4") (pin "B3") (pinfunction "B3_B3") (pintype "passive"))
      (node (ref "J4") (pin "B4") (pinfunction "B4_B4") (pintype "passive"))
      (node (ref "J4") (pin "B5") (pinfunction "B5_B5") (pintype "passive"))
      (node (ref "J5") (pin "A1") (pinfunction "A1_A1") (pintype "passive"))
      (node (ref "J5") (pin "A2") (pinfunction "A2_A2") (pintype "passive"))
      (node (ref "J5") (pin "A3") (pinfunction "A3_A3") (pintype "passive"))
      (node (ref "J5") (pin "A4") (pinfunction "A4_A4") (pintype "passive"))
      (node (ref "J5") (pin "A5") (pinfunction "A5_A5") (pintype "passive"))
      (node (ref "J5") (pin "B1") (pinfunction "B1_B1") (pintype "passive"))
      (node (ref "J5") (pin "B2") (pinfunction "B2_B2") (pintype "passive"))
      (node (ref "J5") (pin "B3") (pinfunction "B3_B3") (pintype "passive"))
      (node (ref "J5") (pin "B4") (pinfunction "B4_B4") (pintype "passive"))
      (node (ref "J5") (pin "B5") (pinfunction "B5_B5") (pintype "passive"))
      (node (ref "J6") (pin "A1") (pinfunction "A1_A1") (pintype "passive"))
      (node (ref "J6") (pin "A12") (pinfunction "A12_A12") (pintype "passive"))
      (node (ref "J6") (pin "A13") (pinfunction "A13_A13") (pintype "passive"))
      (node (ref "J6") (pin "A14") (pinfunction "A14_A14") (pintype "passive"))
      (node (ref "J6") (pin "A15") (pinfunction "A15_A15") (pintype "passive"))
      (node (ref "J6") (pin "A18") (pinfunction "A18_A18") (pintype "passive"))
      (node (ref "J6") (pin "A19") (pinfunction "A19_A19") (pintype "passive"))
      (node (ref "J6") (pin "A2") (pinfunction "A2_A2") (pintype "passive"))
      (node (ref "J6") (pin "A3") (pinfunction "A3_A3") (pintype "passive"))
      (node (ref "J6") (pin "A4") (pinfunction "A4_A4") (pintype "passive"))
      (node (ref "J6") (pin "A5") (pinfunction "A5_A5") (pintype "passive"))
      (node (ref "J6") (pin "A6") (pinfunction "A6_A6") (pintype "passive"))
      (node (ref "J6") (pin "B1") (pinfunction "B1_B1") (pintype "passive"))
      (node (ref "J6") (pin "B12") (pinfunction "B12_B12") (pintype "passive"))
      (node (ref "J6") (pin "B13") (pinfunction "B13_B13") (pintype "passive"))
      (node (ref "J6") (pin "B14") (pinfunction "B14_B14") (pintype "passive"))
      (node (ref "J6") (pin "B15") (pinfunction "B15_B15") (pintype "passive"))
      (node (ref "J6") (pin "B16") (pinfunction "B16_B16") (pintype "passive"))
      (node (ref "J6") (pin "B17") (pinfunction "B17_B17") (pintype "passive"))
      (node (ref "J6") (pin "B2") (pinfunction "B2_B2") (pintype "passive"))
      (node (ref "J6") (pin "B3") (pinfunction "B3_B3") (pintype "passive"))
      (node (ref "J6") (pin "B4") (pinfunction "B4_B4") (pintype "passive"))
      (node (ref "J6") (pin "B5") (pinfunction "B5_B5") (pintype "passive"))
      (node (ref "J6") (pin "B6") (pinfunction "B6_B6") (pintype "passive"))
      (node (ref "J7") (pin "1") (pinfunction "1_1") (pintype "passive"))
      (node (ref "J7") (pin "10") (pinfunction "10_10") (pintype "passive"))
      (node (ref "J7") (pin "2") (pinfunction "2_2") (pintype "passive"))
      (node (ref "J7") (pin "7") (pinfunction "7_7") (pintype "passive"))
      (node (ref "J8") (pin "1") (pinfunction "1_1") (pintype "passive"))
      (node (ref "PC_GND") (pin "1") (pinfunction "1_1") (pintype "passive"))
      (node (ref "U30") (pin "2") (pinfunction "GND_2") (pintype "passive"))
      (node (ref "U30") (pin "3") (pinfunction "CTL_3") (pintype "passive"))
    )
    (net (code "38") (name "Net-(19V_IN-Pad1)") (class "Default")
      (node (ref "19V_IN") (pin "1") (pinfunction "1_1") (pintype "passive"))
      (node (ref "C31") (pin "1") (pinfunction "1_1") (pintype "passive"))
      (node (ref "Q31") (pin "5") (pinfunction "5_5") (pintype "passive"))
      (node (ref "Q31") (pin "6") (pinfunction "6_6") (pintype "passive"))
      (node (ref "Q31") (pin "7") (pinfunction "7_7") (pintype "passive"))
      (node (ref "Q31") (pin "8") (pinfunction "8_8") (pintype "passive"))
    )
    (net (code "39") (name "Net-(U30-GATE)") (class "Default")
      (node (ref "Q30") (pin "4") (pinfunction "4_4") (pintype "passive"))
      (node (ref "U30") (pin "5") (pinfunction "GATE_5") (pintype "passive"))
    )
    (net (code "40") (name "Net-(U30-STAT)") (class "Default")
      (node (ref "Q31") (pin "4") (pinfunction "4_4") (pintype "passive"))
      (node (ref "R30") (pin "1") (pinfunction "1_1") (pintype "passive"))
      (node (ref "U30") (pin "4") (pinfunction "STAT_4") (pintype "passive"))
    )
    (net (code "41") (name "Net-(U30-VIN)") (class "Default")
      (node (ref "16V") (pin "1") (pinfunction "1_1") (pintype "passive"))
      (node (ref "C30") (pin "1") (pinfunction "1_1") (pintype "passive"))
      (node (ref "Q30") (pin "5") (pinfunction "5_5") (pintype "passive"))
      (node (ref "Q30") (pin "6") (pinfunction "6_6") (pintype "passive"))
      (node (ref "Q30") (pin "7") (pinfunction "7_7") (pintype "passive"))
      (node (ref "Q30") (pin "8") (pinfunction "8_8") (pintype "passive"))
      (node (ref "U30") (pin "1") (pinfunction "VIN_1") (pintype "passive"))
    )
    (net (code "42") (name "unconnected-(J1-PadA6)") (class "Default")
      (node (ref "J1") (pin "A6") (pinfunction "A6_A6") (pintype "passive"))
    )
    (net (code "43") (name "unconnected-(J1-PadB6)") (class "Default")
      (node (ref "J1") (pin "B6") (pinfunction "B6_B6") (pintype "passive"))
    )
    (net (code "44") (name "unconnected-(J2-PadA6)") (class "Default")
      (node (ref "J2") (pin "A6") (pinfunction "A6_A6") (pintype "passive"))
    )
    (net (code "45") (name "unconnected-(J2-PadB6)") (class "Default")
      (node (ref "J2") (pin "B6") (pinfunction "B6_B6") (pintype "passive"))
    )
    (net (code "46") (name "unconnected-(J3-PadA6)") (class "Default")
      (node (ref "J3") (pin "A6") (pinfunction "A6_A6") (pintype "passive"))
    )
    (net (code "47") (name "unconnected-(J3-PadB6)") (class "Default")
      (node (ref "J3") (pin "B6") (pinfunction "B6_B6") (pintype "passive"))
    )
    (net (code "48") (name "unconnected-(J4-PadA6)") (class "Default")
      (node (ref "J4") (pin "A6") (pinfunction "A6_A6") (pintype "passive"))
    )
    (net (code "49") (name "unconnected-(J4-PadB6)") (class "Default")
      (node (ref "J4") (pin "B6") (pinfunction "B6_B6") (pintype "passive"))
    )
    (net (code "50") (name "unconnected-(J5-PadA6)") (class "Default")
      (node (ref "J5") (pin "A6") (pinfunction "A6_A6") (pintype "passive"))
    )
    (net (code "51") (name "unconnected-(J5-PadB6)") (class "Default")
      (node (ref "J5") (pin "B6") (pinfunction "B6_B6") (pintype "passive"))
    )
    (net (code "52") (name "unconnected-(J6-PadA20)") (class "Default")
      (node (ref "J6") (pin "A20") (pinfunction "A20_A20") (pintype "passive"))
    )
    (net (code "53") (name "unconnected-(J6-PadA21)") (class "Default")
      (node (ref "J6") (pin "A21") (pinfunction "A21_A21") (pintype "passive"))
    )
    (net (code "54") (name "unconnected-(J6-PadA22)") (class "Default")
      (node (ref "J6") (pin "A22") (pinfunction "A22_A22") (pintype "passive"))
    )
    (net (code "55") (name "unconnected-(J6-PadA23)") (class "Default")
      (node (ref "J6") (pin "A23") (pinfunction "A23_A23") (pintype "passive"))
    )
    (net (code "56") (name "unconnected-(J6-PadA24)") (class "Default")
      (node (ref "J6") (pin "A24") (pinfunction "A24_A24") (pintype "passive"))
    )
    (net (code "57") (name "unconnected-(J6-PadA25)") (class "Default")
      (node (ref "J6") (pin "A25") (pinfunction "A25_A25") (pintype "passive"))
    )
    (net (code "58") (name "unconnected-(J6-PadA26)") (class "Default")
      (node (ref "J6") (pin "A26") (pinfunction "A26_A26") (pintype "passive"))
    )
    (net (code "59") (name "unconnected-(J6-PadA27)") (class "Default")
      (node (ref "J6") (pin "A27") (pinfunction "A27_A27") (pintype "passive"))
    )
    (net (code "60") (name "unconnected-(J6-PadA28)") (class "Default")
      (node (ref "J6") (pin "A28") (pinfunction "A28_A28") (pintype "passive"))
    )
    (net (code "61") (name "unconnected-(J30-Pad1)") (class "Default")
      (node (ref "J30") (pin "1") (pinfunction "1_1") (pintype "passive"))
    )
    (net (code "62") (name "unconnected-(J31-Pad1)") (class "Default")
      (node (ref "J31") (pin "1") (pinfunction "1_1") (pintype "passive"))
    )
  )
)
